# HEART_RATE.net
KiCad netlist of a schematic drawn in Altium Designer
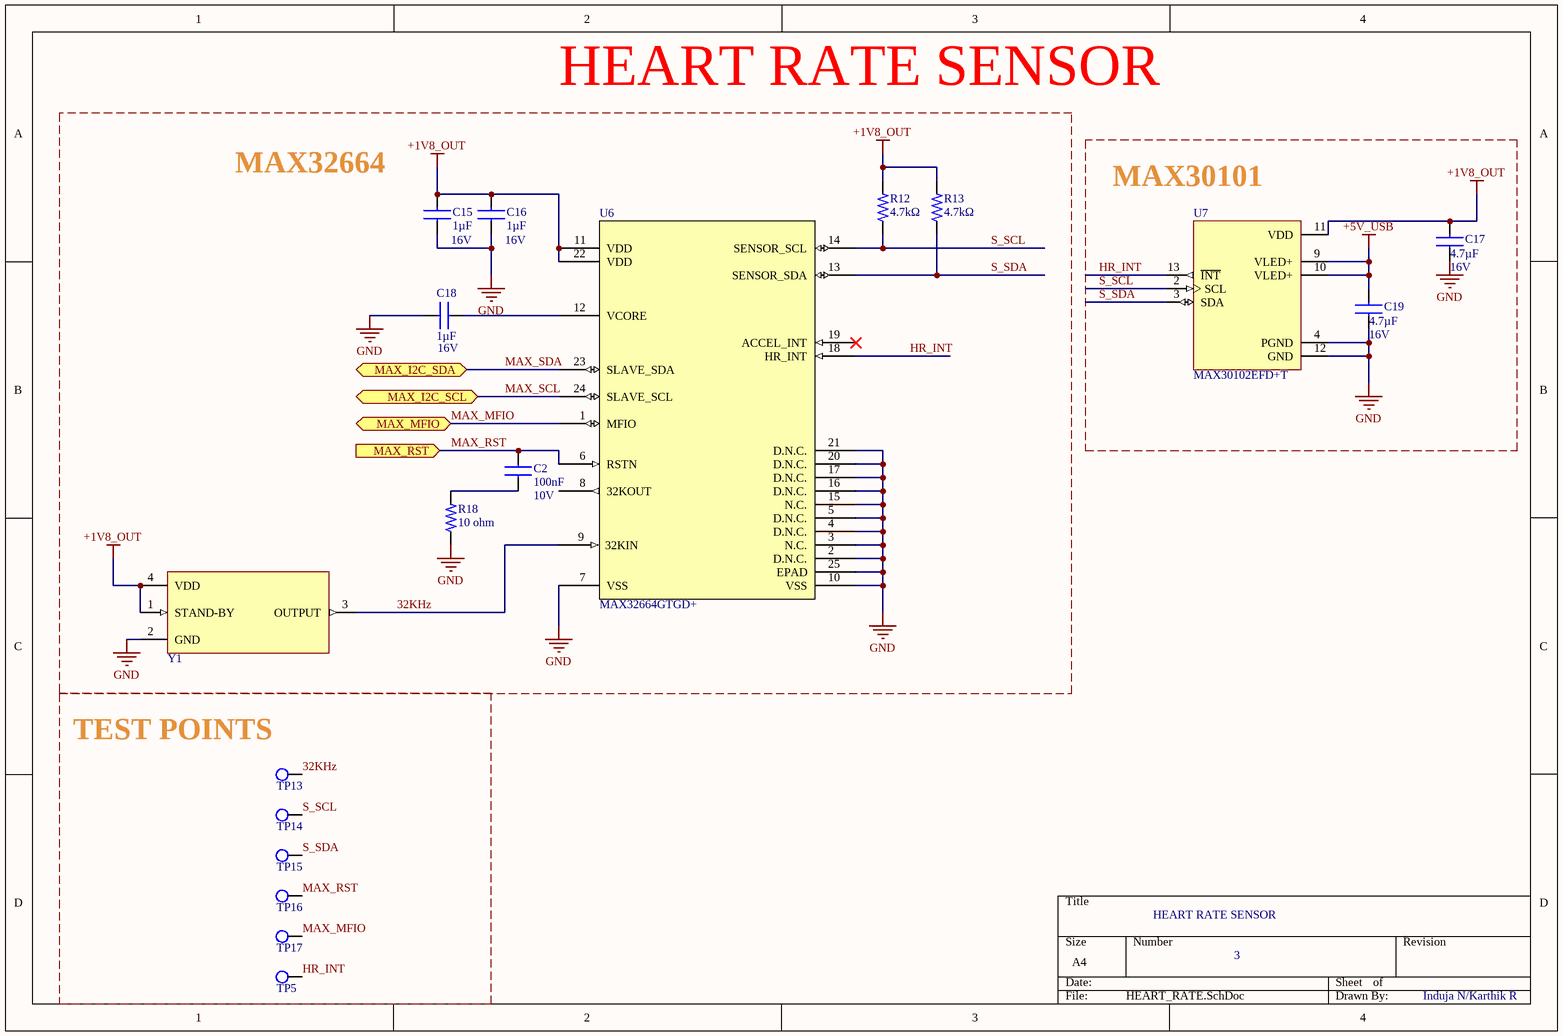
[diagram p0: HEART_RATE.SchDoc]

(export (version "E")
  (design (tool "Eeschema 10.0.6"))
  (components
    (comp (ref "C2")
      (value "100nF")
      (footprint "CAP_0603_1MM")
      (description "0603 0.1 uF 10 V ±10% Tolerance X7R SMT Multilayer Ceramic Chip Capacitor")
      (fields
        (field (name "MANUFACTURER") "Vishay")
        (field (name "MANUFACTURER PART NUMBER") "VJ0603Y104KXQCW1BC")
        (field (name "VOLTAGE RATING (DC)") "10V")
      )
      (libsource (lib "LPEDT_Components") (part "CAP 0.1uF 0603"))
    )
    (comp (ref "C15")
      (value "1µF")
      (footprint "Capacitor 0603")
      (description "16V 1uF X7R ±10% 0603 Multilayer Ceramic Capacitors MLCC - SMD/SMT ROHS")
      (fields
        (field (name "MANUFACTURER") "Samsung Electro-Mechanics")
        (field (name "MANUFACTURER PART NUMBER") "CL10B105KO8NNNC")
        (field (name "VOLTAGE RATING") "16V")
      )
      (libsource (lib "LPEDT_Components") (part "CAP 1uF 0603"))
    )
    (comp (ref "C16")
      (value "1µF")
      (footprint "Capacitor 0603")
      (description "16V 1uF X7R ±10% 0603 Multilayer Ceramic Capacitors MLCC - SMD/SMT ROHS")
      (fields
        (field (name "MANUFACTURER") "Samsung Electro-Mechanics")
        (field (name "MANUFACTURER PART NUMBER") "CL10B105KO8NNNC")
        (field (name "VOLTAGE RATING") "16V")
      )
      (libsource (lib "LPEDT_Components") (part "CAP 1uF 0603"))
    )
    (comp (ref "C17")
      (value "4.7µF")
      (footprint "Capacitor 0603")
      (description "16V 4.7uF X7R ±10% 0603 Multilayer Ceramic Capacitors MLCC - SMD/SMT ROHS")
      (fields
        (field (name "MANUFACTURER") "Murata")
        (field (name "MANUFACTURER PART NUMBER") "GRM188Z71C475KE21D")
        (field (name "VOLTAGE RATING (DC)") "16V")
      )
      (libsource (lib "LPEDT_Components") (part "CAP 4.7uF 16V X7R"))
    )
    (comp (ref "C18")
      (value "1µF")
      (footprint "Capacitor 0603")
      (description "16V 1uF X7R ±10% 0603 Multilayer Ceramic Capacitors MLCC - SMD/SMT ROHS")
      (fields
        (field (name "MANUFACTURER") "Samsung Electro-Mechanics")
        (field (name "MANUFACTURER PART NUMBER") "CL10B105KO8NNNC")
        (field (name "VOLTAGE") "16V")
      )
      (libsource (lib "LPEDT_Components") (part "CAP 1uF 0603"))
    )
    (comp (ref "C19")
      (value "4.7µF")
      (footprint "Capacitor 0603")
      (description "16V 4.7uF X7R ±10% 0603 Multilayer Ceramic Capacitors MLCC - SMD/SMT ROHS")
      (fields
        (field (name "MANUFACTURER") "Murata")
        (field (name "MANUFACTURER PART NUMBER") "GRM188Z71C475KE21D")
        (field (name "VOLTAGE RATING (DC)") "16V")
      )
      (libsource (lib "LPEDT_Components") (part "CAP 4.7uF 16V X7R"))
    )
    (comp (ref "R12")
      (value "4.7kΩ")
      (footprint "RES_0603_1608X06")
      (fields
        (field (name "MANUFACTURER") "Yageo")
        (field (name "MANUFACTURER PART NUMBER") "RC0603FR-074K7L")
        (field (name "TOLERANCE") "1%")
      )
      (libsource (lib "LPEDT_Components") (part "RES 4.7K 0603"))
    )
    (comp (ref "R13")
      (value "4.7kΩ")
      (footprint "RES_0603_1608X06")
      (fields
        (field (name "MANUFACTURER") "Yageo")
        (field (name "MANUFACTURER PART NUMBER") "RC0603FR-074K7L")
        (field (name "TOLERANCE") "1%")
      )
      (libsource (lib "LPEDT_Components") (part "RES 4.7K 0603"))
    )
    (comp (ref "R18")
      (value "10 ohm")
      (footprint "RES_0603_1608X06")
      (description "10 Ohm CMP-2000-03846-1")
      (fields (field (name "PART NUMBER") "CRCW060310R0FKEAHP") (field (name "MANUFACTURER") "Vishay Dale"))
      (libsource (lib "LPEDT_Components") (part "RES 10 ohm"))
    )
    (comp (ref "TP5")
      (value "Test Point")
      (footprint "Test Point")
      (libsource (lib "LPEDT_Components") (part "Test Point"))
    )
    (comp (ref "TP13")
      (value "Test Point")
      (footprint "Test Point")
      (libsource (lib "LPEDT_Components") (part "Test Point"))
    )
    (comp (ref "TP14")
      (value "Test Point")
      (footprint "Test Point")
      (libsource (lib "LPEDT_Components") (part "Test Point"))
    )
    (comp (ref "TP15")
      (value "Test Point")
      (footprint "Test Point")
      (libsource (lib "LPEDT_Components") (part "Test Point"))
    )
    (comp (ref "TP16")
      (value "Test Point")
      (footprint "Test Point")
      (libsource (lib "LPEDT_Components") (part "Test Point"))
    )
    (comp (ref "TP17")
      (value "Test Point")
      (footprint "Test Point")
      (libsource (lib "LPEDT_Components") (part "Test Point"))
    )
    (comp (ref "U6")
      (value "MAX32664GTGD+")
      (footprint "21-100264_T2433+2C_MXM")
      (description "Ultra-Low Power Biometric Sensor Hub")
      (fields (field (name "COPYRIGHT") "Copyright (C) 2025 Ultra Librarian. All rights reserved."))
      (libsource (lib "LPEDT_Components") (part "MAX32664GTGD+"))
    )
    (comp (ref "U7")
      (value "MAX30102EFD+T")
      (footprint "XDCR_MAX30101EFD+")
      (description "SENSOR - OXIMETER/HEART RATE I2C")
      (fields
        (field (name "DIGI-KEY_PART_NUMBER") "MAX30102EFD+TTR-ND")
        (field (name "MF") "Maxim Integrated Products")
      )
      (libsource (lib "LPEDT_Components") (part "MAX30102EFD+T"))
    )
    (comp (ref "Y1")
      (value "ECS-327MV-DM-TR")
      (footprint "OSC_ECS-327MV-DM-TR-4")
      (description "32.768 kHz XO (Standard) CMOS Oscillator Enable/Disable 4-SMD, No Lead")
      (fields (field (name "MF") "ECS Inc.") (field (name "DIGI-KEY_PART_NUMBER") "50-ECS-327MV-DM-TR-ND"))
      (libsource (lib "LPEDT_Components") (part "32.768 kHz"))
    )
  )
  (nets
    (net (code "1") (name "+1V8_OUT") (class "Default")
      (node (ref "C15") (pin "1") (pinfunction "1_1") (pintype "passive"))
      (node (ref "C16") (pin "1") (pinfunction "1_1") (pintype "passive"))
      (node (ref "C17") (pin "1") (pinfunction "1_1") (pintype "passive"))
      (node (ref "R12") (pin "2") (pinfunction "2_2") (pintype "passive"))
      (node (ref "R13") (pin "2") (pinfunction "2_2") (pintype "passive"))
      (node (ref "U6") (pin "11") (pinfunction "VDD_11") (pintype "power_in"))
      (node (ref "U6") (pin "22") (pinfunction "VDD_22") (pintype "power_in"))
      (node (ref "U7") (pin "11") (pinfunction "VDD_11") (pintype "power_in"))
      (node (ref "Y1") (pin "1") (pinfunction "STAND-BY_1") (pintype "input"))
      (node (ref "Y1") (pin "4") (pinfunction "VDD_4") (pintype "power_in"))
    )
    (net (code "2") (name "+5V_USB") (class "Default")
      (node (ref "C19") (pin "1") (pinfunction "1_1") (pintype "passive"))
      (node (ref "U7") (pin "10") (pinfunction "VLED+_10") (pintype "power_in"))
      (node (ref "U7") (pin "9") (pinfunction "VLED+_9") (pintype "power_in"))
    )
    (net (code "3") (name "/32KHz") (class "Default")
      (node (ref "TP13") (pin "1") (pinfunction "1_1") (pintype "passive"))
      (node (ref "U6") (pin "9") (pinfunction "32KIN_9") (pintype "input"))
      (node (ref "Y1") (pin "3") (pinfunction "OUTPUT_3") (pintype "output"))
    )
    (net (code "4") (name "/HR_INT") (class "Default")
      (node (ref "TP5") (pin "1") (pinfunction "1_1") (pintype "passive"))
      (node (ref "U6") (pin "18") (pinfunction "HR_INT_18") (pintype "input"))
      (node (ref "U7") (pin "13") (pinfunction "~{INT}_13") (pintype "output"))
    )
    (net (code "5") (name "/MAX_MFIO") (class "Default")
      (node (ref "TP17") (pin "1") (pinfunction "1_1") (pintype "passive"))
      (node (ref "U6") (pin "1") (pinfunction "MFIO_1") (pintype "bidirectional"))
    )
    (net (code "6") (name "/MAX_RST") (class "Default")
      (node (ref "C2") (pin "1") (pinfunction "1_1") (pintype "passive"))
      (node (ref "TP16") (pin "1") (pinfunction "1_1") (pintype "passive"))
      (node (ref "U6") (pin "6") (pinfunction "RSTN_6") (pintype "input"))
    )
    (net (code "7") (name "/MAX_SCL") (class "Default")
      (node (ref "U6") (pin "24") (pinfunction "SLAVE_SCL_24") (pintype "bidirectional"))
    )
    (net (code "8") (name "/MAX_SDA") (class "Default")
      (node (ref "U6") (pin "23") (pinfunction "SLAVE_SDA_23") (pintype "bidirectional"))
    )
    (net (code "9") (name "/S_SCL") (class "Default")
      (node (ref "R12") (pin "1") (pinfunction "1_1") (pintype "passive"))
      (node (ref "TP14") (pin "1") (pinfunction "1_1") (pintype "passive"))
      (node (ref "U6") (pin "14") (pinfunction "SENSOR_SCL_14") (pintype "bidirectional"))
      (node (ref "U7") (pin "2") (pinfunction "SCL_2") (pintype "input"))
    )
    (net (code "10") (name "/S_SDA") (class "Default")
      (node (ref "R13") (pin "1") (pinfunction "1_1") (pintype "passive"))
      (node (ref "TP15") (pin "1") (pinfunction "1_1") (pintype "passive"))
      (node (ref "U6") (pin "13") (pinfunction "SENSOR_SDA_13") (pintype "bidirectional"))
      (node (ref "U7") (pin "3") (pinfunction "SDA_3") (pintype "bidirectional"))
    )
    (net (code "11") (name "GND") (class "Default")
      (node (ref "C15") (pin "2") (pinfunction "2_2") (pintype "passive"))
      (node (ref "C16") (pin "2") (pinfunction "2_2") (pintype "passive"))
      (node (ref "C17") (pin "2") (pinfunction "2_2") (pintype "passive"))
      (node (ref "C18") (pin "2") (pinfunction "2_2") (pintype "passive"))
      (node (ref "C19") (pin "2") (pinfunction "2_2") (pintype "passive"))
      (node (ref "R18") (pin "1") (pinfunction "1_1") (pintype "passive"))
      (node (ref "U6") (pin "10") (pinfunction "VSS_10") (pintype "power_in"))
      (node (ref "U6") (pin "15") (pinfunction "N.C._15") (pintype "passive"))
      (node (ref "U6") (pin "16") (pinfunction "D.N.C._16") (pintype "passive"))
      (node (ref "U6") (pin "17") (pinfunction "D.N.C._17") (pintype "passive"))
      (node (ref "U6") (pin "2") (pinfunction "D.N.C._2") (pintype "passive"))
      (node (ref "U6") (pin "20") (pinfunction "D.N.C._20") (pintype "passive"))
      (node (ref "U6") (pin "21") (pinfunction "D.N.C._21") (pintype "passive"))
      (node (ref "U6") (pin "25") (pinfunction "EPAD_25") (pintype "power_in"))
      (node (ref "U6") (pin "3") (pinfunction "N.C._3") (pintype "passive"))
      (node (ref "U6") (pin "4") (pinfunction "D.N.C._4") (pintype "passive"))
      (node (ref "U6") (pin "5") (pinfunction "D.N.C._5") (pintype "passive"))
      (node (ref "U6") (pin "7") (pinfunction "VSS_7") (pintype "power_in"))
      (node (ref "U7") (pin "12") (pinfunction "GND_12") (pintype "power_in"))
      (node (ref "U7") (pin "4") (pinfunction "PGND_4") (pintype "power_in"))
      (node (ref "Y1") (pin "2") (pinfunction "GND_2") (pintype "power_in"))
    )
    (net (code "12") (name "Net-(C2-Pad2)") (class "Default")
      (node (ref "C2") (pin "2") (pinfunction "2_2") (pintype "passive"))
      (node (ref "R18") (pin "2") (pinfunction "2_2") (pintype "passive"))
    )
    (net (code "13") (name "Net-(U6-VCORE)") (class "Default")
      (node (ref "C18") (pin "1") (pinfunction "1_1") (pintype "passive"))
      (node (ref "U6") (pin "12") (pinfunction "VCORE_12") (pintype "power_in"))
    )
    (net (code "14") (name "unconnected-(U6-32KOUT-Pad8)") (class "Default")
      (node (ref "U6") (pin "8") (pinfunction "32KOUT_8") (pintype "output"))
    )
    (net (code "15") (name "unconnected-(U6-ACCEL_INT-Pad19)") (class "Default")
      (node (ref "U6") (pin "19") (pinfunction "ACCEL_INT_19") (pintype "input+no_connect"))
    )
  )
)
